# esp12f.net
KiCad netlist of a schematic drawn in Altium Designer
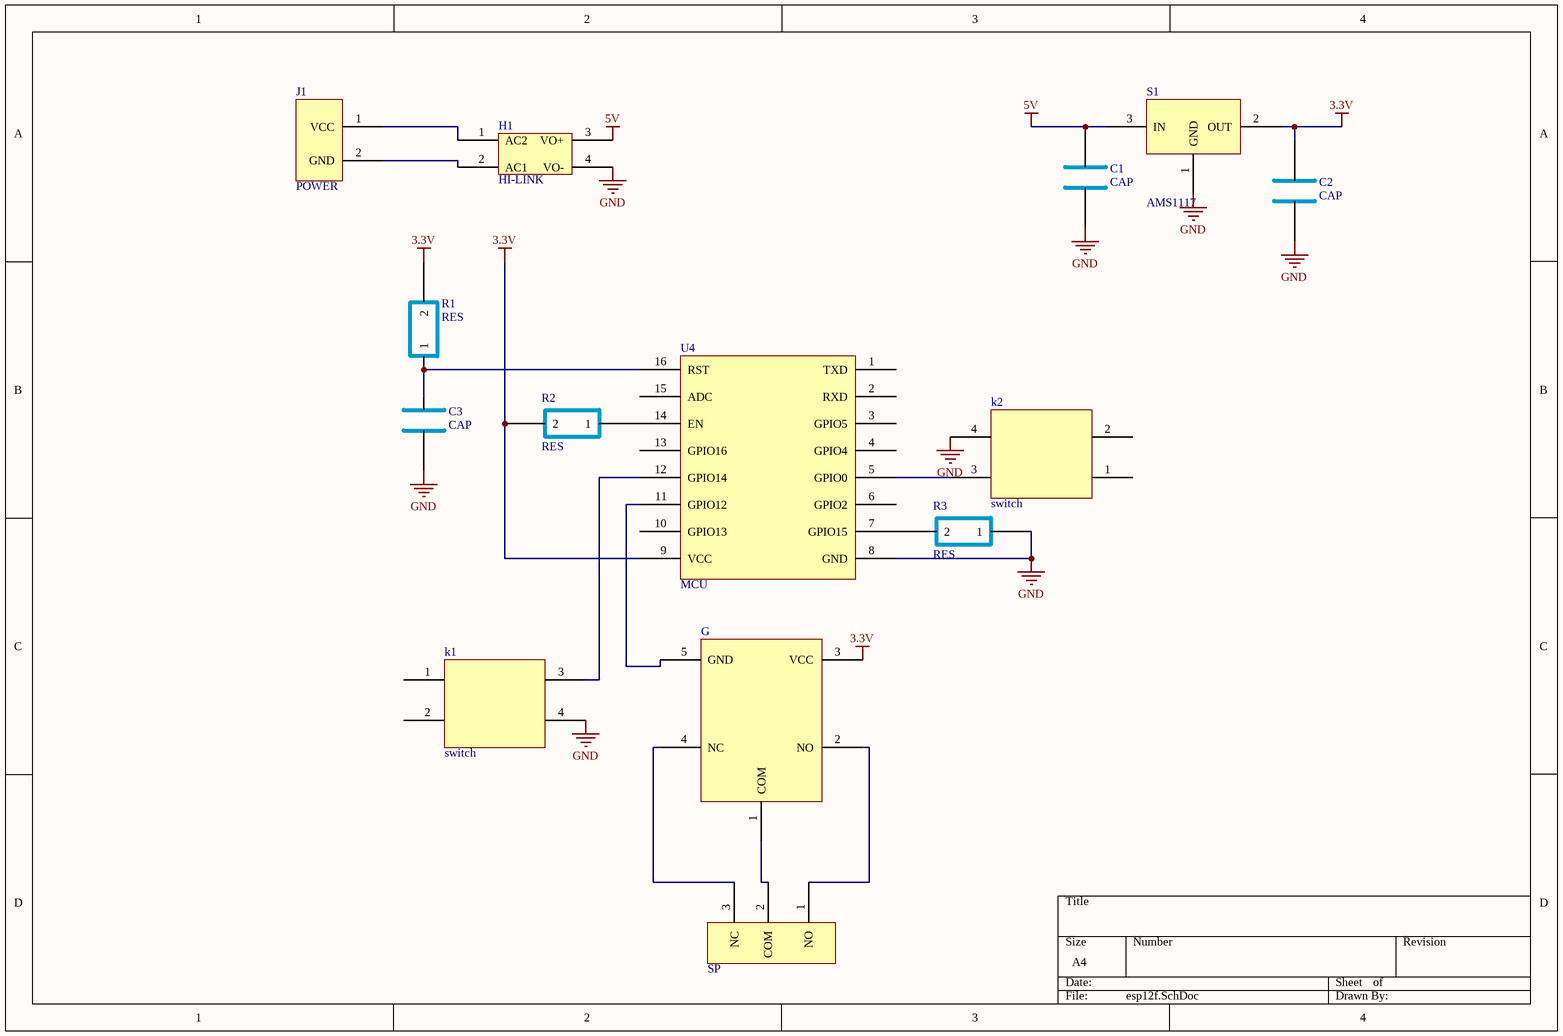
[diagram p0: esp12f.SchDoc]

(export (version "E")
  (design (tool "Eeschema 10.0.6"))
  (components
    (comp (ref "C1") (value "CAP") (footprint "CB2") (libsource (lib "esp12F") (part "CAP")))
    (comp (ref "C2") (value "CAP") (footprint "CB2") (libsource (lib "esp12F") (part "CAP")))
    (comp (ref "C3") (value "CAP") (footprint "CB2") (libsource (lib "esp12F") (part "CAP")))
    (comp (ref "G") (value "jidianqi") (footprint "jidianqi") (libsource (lib "esp12F") (part "jidianqi")))
    (comp (ref "H1") (value "HI-LINK") (footprint "Hi-Link") (libsource (lib "esp12F") (part "HI-LINK")))
    (comp (ref "J1") (value "POWER") (footprint "SIP02") (libsource (lib "esp12F") (part "CON2")))
    (comp (ref "k1") (value "switch") (footprint "SWITCH") (libsource (lib "") (part "switch_1")))
    (comp (ref "k2") (value "switch") (footprint "SWITCH") (libsource (lib "esp12F") (part "switch")))
    (comp (ref "R1") (value "RES") (footprint "RAD0.3") (libsource (lib "esp12F") (part "RES")))
    (comp (ref "R2") (value "RES") (footprint "RAD0.3") (libsource (lib "esp12F") (part "RES")))
    (comp (ref "R3") (value "RES") (footprint "RAD0.3") (libsource (lib "esp12F") (part "RES")))
    (comp (ref "S1") (value "AMS1117") (libsource (lib "esp12F") (part "AMS1117")))
    (comp (ref "SP") (value "SPI3") (footprint "SIPX03") (libsource (lib "esp12F") (part "SPI3")))
    (comp (ref "U4") (value "MCU") (footprint "esp12f") (libsource (lib "esp12F") (part "ESP12F")))
  )
  (nets
    (net (code "1") (name "3.3V") (class "Default")
      (node (ref "C2") (pin "1") (pinfunction "1_1") (pintype "passive"))
      (node (ref "G") (pin "3") (pinfunction "VCC_3") (pintype "passive"))
      (node (ref "R1") (pin "2") (pinfunction "2_2") (pintype "passive"))
      (node (ref "R2") (pin "2") (pinfunction "2_2") (pintype "passive"))
      (node (ref "S1") (pin "2") (pinfunction "OUT_2") (pintype "passive"))
      (node (ref "U4") (pin "9") (pinfunction "VCC_9") (pintype "passive"))
    )
    (net (code "2") (name "5V") (class "Default")
      (node (ref "C1") (pin "1") (pinfunction "1_1") (pintype "passive"))
      (node (ref "H1") (pin "3") (pinfunction "VO+_3") (pintype "passive"))
      (node (ref "S1") (pin "3") (pinfunction "IN_3") (pintype "passive"))
    )
    (net (code "3") (name "GND") (class "Default")
      (node (ref "C1") (pin "2") (pinfunction "2_2") (pintype "passive"))
      (node (ref "C2") (pin "2") (pinfunction "2_2") (pintype "passive"))
      (node (ref "C3") (pin "2") (pinfunction "2_2") (pintype "passive"))
      (node (ref "H1") (pin "4") (pinfunction "VO-_4") (pintype "passive"))
      (node (ref "R3") (pin "1") (pinfunction "1_1") (pintype "passive"))
      (node (ref "S1") (pin "1") (pinfunction "GND_1") (pintype "passive"))
      (node (ref "U4") (pin "8") (pinfunction "GND_8") (pintype "passive"))
      (node (ref "k1") (pin "4") (pinfunction "26_4") (pintype "passive"))
      (node (ref "k2") (pin "4") (pinfunction "26_4") (pintype "passive"))
    )
    (net (code "4") (name "Net-(G-COM)") (class "Default")
      (node (ref "G") (pin "1") (pinfunction "COM_1") (pintype "passive"))
      (node (ref "SP") (pin "2") (pinfunction "COM_2") (pintype "passive"))
    )
    (net (code "5") (name "Net-(G-GND)") (class "Default")
      (node (ref "G") (pin "5") (pinfunction "GND_5") (pintype "passive"))
      (node (ref "U4") (pin "11") (pinfunction "GPIO12_11") (pintype "passive"))
    )
    (net (code "6") (name "Net-(G-NC)") (class "Default")
      (node (ref "G") (pin "4") (pinfunction "NC_4") (pintype "passive"))
      (node (ref "SP") (pin "3") (pinfunction "NC_3") (pintype "passive"))
    )
    (net (code "7") (name "Net-(G-NO)") (class "Default")
      (node (ref "G") (pin "2") (pinfunction "NO_2") (pintype "passive"))
      (node (ref "SP") (pin "1") (pinfunction "NO_1") (pintype "passive"))
    )
    (net (code "8") (name "Net-(H1-AC1)") (class "Default")
      (node (ref "H1") (pin "2") (pinfunction "AC1_2") (pintype "passive"))
      (node (ref "J1") (pin "2") (pinfunction "GND_2") (pintype "passive"))
    )
    (net (code "9") (name "Net-(H1-AC2)") (class "Default")
      (node (ref "H1") (pin "1") (pinfunction "AC2_1") (pintype "passive"))
      (node (ref "J1") (pin "1") (pinfunction "VCC_1") (pintype "passive"))
    )
    (net (code "10") (name "Net-(U4-EN)") (class "Default")
      (node (ref "R2") (pin "1") (pinfunction "1_1") (pintype "passive"))
      (node (ref "U4") (pin "14") (pinfunction "EN_14") (pintype "passive"))
    )
    (net (code "11") (name "Net-(U4-GPIO0)") (class "Default")
      (node (ref "U4") (pin "5") (pinfunction "GPIO0_5") (pintype "passive"))
      (node (ref "k2") (pin "3") (pinfunction "25_3") (pintype "passive"))
    )
    (net (code "12") (name "Net-(U4-GPIO14)") (class "Default")
      (node (ref "U4") (pin "12") (pinfunction "GPIO14_12") (pintype "passive"))
      (node (ref "k1") (pin "3") (pinfunction "25_3") (pintype "passive"))
    )
    (net (code "13") (name "Net-(U4-GPIO15)") (class "Default")
      (node (ref "R3") (pin "2") (pinfunction "2_2") (pintype "passive"))
      (node (ref "U4") (pin "7") (pinfunction "GPIO15_7") (pintype "passive"))
    )
    (net (code "14") (name "Net-(U4-RST)") (class "Default")
      (node (ref "C3") (pin "1") (pinfunction "1_1") (pintype "passive"))
      (node (ref "R1") (pin "1") (pinfunction "1_1") (pintype "passive"))
      (node (ref "U4") (pin "16") (pinfunction "RST_16") (pintype "passive"))
    )
    (net (code "15") (name "unconnected-(U4-ADC-Pad15)") (class "Default")
      (node (ref "U4") (pin "15") (pinfunction "ADC_15") (pintype "passive"))
    )
    (net (code "16") (name "unconnected-(U4-GPIO2-Pad6)") (class "Default")
      (node (ref "U4") (pin "6") (pinfunction "GPIO2_6") (pintype "passive"))
    )
    (net (code "17") (name "unconnected-(U4-GPIO4-Pad4)") (class "Default")
      (node (ref "U4") (pin "4") (pinfunction "GPIO4_4") (pintype "passive"))
    )
    (net (code "18") (name "unconnected-(U4-GPIO5-Pad3)") (class "Default")
      (node (ref "U4") (pin "3") (pinfunction "GPIO5_3") (pintype "passive"))
    )
    (net (code "19") (name "unconnected-(U4-GPIO13-Pad10)") (class "Default")
      (node (ref "U4") (pin "10") (pinfunction "GPIO13_10") (pintype "passive"))
    )
    (net (code "20") (name "unconnected-(U4-GPIO16-Pad13)") (class "Default")
      (node (ref "U4") (pin "13") (pinfunction "GPIO16_13") (pintype "passive"))
    )
    (net (code "21") (name "unconnected-(U4-RXD-Pad2)") (class "Default")
      (node (ref "U4") (pin "2") (pinfunction "RXD_2") (pintype "passive"))
    )
    (net (code "22") (name "unconnected-(U4-TXD-Pad1)") (class "Default")
      (node (ref "U4") (pin "1") (pinfunction "TXD_1") (pintype "passive"))
    )
    (net (code "23") (name "unconnected-(k1-24-Pad2)") (class "Default")
      (node (ref "k1") (pin "2") (pinfunction "24_2") (pintype "passive"))
    )
    (net (code "24") (name "unconnected-(k1-Pad1)") (class "Default")
      (node (ref "k1") (pin "1") (pinfunction "1_1") (pintype "passive"))
    )
    (net (code "25") (name "unconnected-(k2-24-Pad2)") (class "Default")
      (node (ref "k2") (pin "2") (pinfunction "24_2") (pintype "passive"))
    )
    (net (code "26") (name "unconnected-(k2-Pad1)") (class "Default")
      (node (ref "k2") (pin "1") (pinfunction "1_1") (pintype "passive"))
    )
  )
)
